# DSO_ADC.net
KiCad netlist of a schematic drawn in Altium Designer
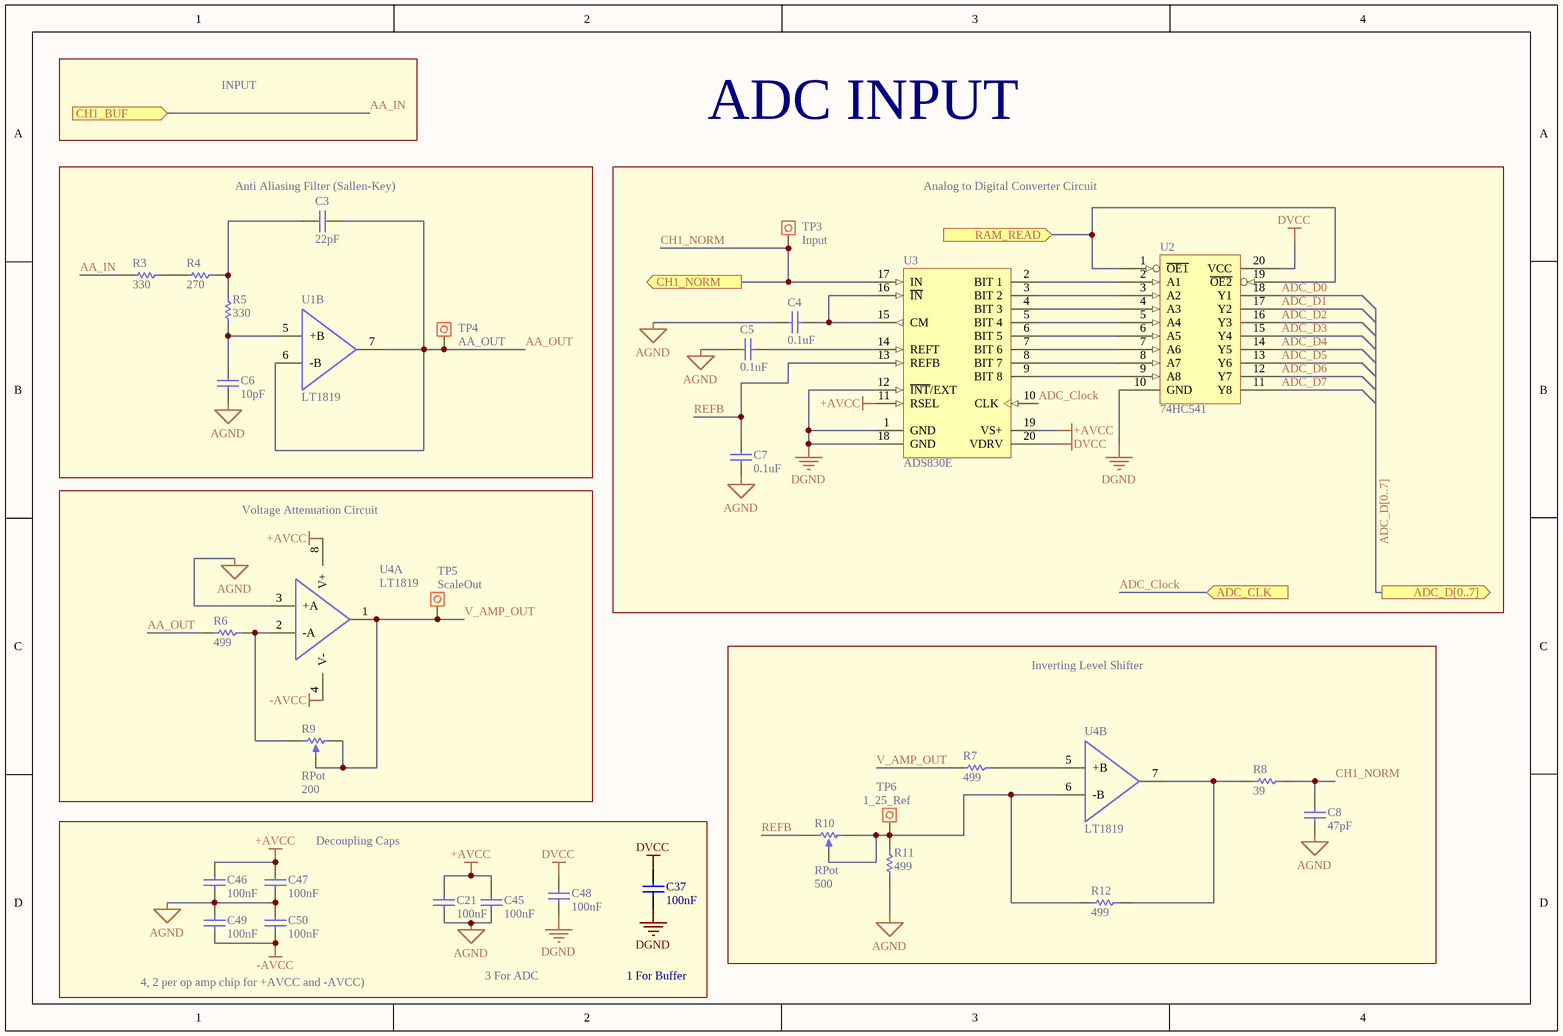
[diagram p0: DSO_ADC.SchDoc]

(export (version "E")
  (design (tool "Eeschema 10.0.6"))
  (components
    (comp (ref "C3")
      (value "22pF")
      (footprint "0805C")
      (description "Capacitor")
      (fields (field (name "REVIEWED BY") "RM - 2018/08/05"))
      (libsource (lib "DSO") (part "C"))
    )
    (comp (ref "C4")
      (value "0.1uF")
      (footprint "0805C")
      (description "Capacitor")
      (fields (field (name "REVIEWED BY") "RM - 2018/08/05"))
      (libsource (lib "DSO") (part "C"))
    )
    (comp (ref "C5")
      (value "0.1uF")
      (footprint "0805C")
      (description "Capacitor")
      (fields (field (name "REVIEWED BY") "RM - 2018/08/05"))
      (libsource (lib "DSO") (part "C"))
    )
    (comp (ref "C6")
      (value "10pF")
      (footprint "0805C")
      (description "Capacitor")
      (fields (field (name "REVIEWED BY") "RM - 2018/08/05"))
      (libsource (lib "DSO") (part "C"))
    )
    (comp (ref "C7")
      (value "0.1uF")
      (footprint "0805C")
      (description "Capacitor")
      (fields (field (name "REVIEWED BY") "RM - 2018/08/05"))
      (libsource (lib "DSO") (part "C"))
    )
    (comp (ref "C8")
      (value "47pF")
      (footprint "0805C")
      (description "Capacitor")
      (fields (field (name "REVIEWED BY") "RM - 2018/08/05"))
      (libsource (lib "DSO") (part "C"))
    )
    (comp (ref "C21")
      (value "100nF")
      (footprint "0805C")
      (description "Capacitor")
      (fields (field (name "REVIEWED BY") "RM - 2018/08/05"))
      (libsource (lib "DSO") (part "C"))
    )
    (comp (ref "C37")
      (value "100nF")
      (footprint "0805C")
      (description "Capacitor")
      (fields (field (name "REVIEWED BY") "RM - 2018/08/05"))
      (libsource (lib "DSO") (part "C"))
    )
    (comp (ref "C45")
      (value "100nF")
      (footprint "0805C")
      (description "Capacitor")
      (fields (field (name "REVIEWED BY") "RM - 2018/08/05"))
      (libsource (lib "DSO") (part "C"))
    )
    (comp (ref "C46")
      (value "100nF")
      (footprint "0805C")
      (description "Capacitor")
      (fields (field (name "REVIEWED BY") "RM - 2018/08/05"))
      (libsource (lib "DSO") (part "C"))
    )
    (comp (ref "C47")
      (value "100nF")
      (footprint "0805C")
      (description "Capacitor")
      (fields (field (name "REVIEWED BY") "RM - 2018/08/05"))
      (libsource (lib "DSO") (part "C"))
    )
    (comp (ref "C48")
      (value "100nF")
      (footprint "0805C")
      (description "Capacitor")
      (fields (field (name "REVIEWED BY") "RM - 2018/08/05"))
      (libsource (lib "DSO") (part "C"))
    )
    (comp (ref "C49")
      (value "100nF")
      (footprint "0805C")
      (description "Capacitor")
      (fields (field (name "REVIEWED BY") "RM - 2018/08/05"))
      (libsource (lib "DSO") (part "C"))
    )
    (comp (ref "C50")
      (value "100nF")
      (footprint "0805C")
      (description "Capacitor")
      (fields (field (name "REVIEWED BY") "RM - 2018/08/05"))
      (libsource (lib "DSO") (part "C"))
    )
    (comp (ref "R3")
      (value "330")
      (footprint "0805")
      (description "Resistor")
      (fields (field (name "REVIEWED BY") "RM - 2018/08/05"))
      (libsource (lib "DSO") (part "R"))
    )
    (comp (ref "R4")
      (value "270")
      (footprint "0805")
      (description "Resistor")
      (fields (field (name "REVIEWED BY") "RM - 2018/08/05"))
      (libsource (lib "DSO") (part "R"))
    )
    (comp (ref "R5")
      (value "330")
      (footprint "0805")
      (description "Resistor")
      (fields (field (name "REVIEWED BY") "RM - 2018/08/05"))
      (libsource (lib "DSO") (part "R"))
    )
    (comp (ref "R6")
      (value "499")
      (footprint "0805")
      (description "Resistor")
      (fields (field (name "REVIEWED BY") "RM - 2018/08/05"))
      (libsource (lib "DSO") (part "R"))
    )
    (comp (ref "R7")
      (value "499")
      (footprint "0805")
      (description "Resistor")
      (fields (field (name "REVIEWED BY") "RM - 2018/08/05"))
      (libsource (lib "DSO") (part "R"))
    )
    (comp (ref "R8")
      (value "39")
      (footprint "0805")
      (description "Resistor")
      (fields (field (name "REVIEWED BY") "RM - 2018/08/05"))
      (libsource (lib "DSO") (part "R"))
    )
    (comp (ref "R9")
      (value "RPot")
      (footprint "VR5")
      (description "Potentiometer")
      (fields (field (name "ALTIUM_VALUE") "200") (field (name "PUBLISHER") "Altium Limited"))
      (libsource (lib "DSO") (part "RPot"))
    )
    (comp (ref "R10")
      (value "RPot")
      (footprint "VR5")
      (description "Potentiometer")
      (fields (field (name "ALTIUM_VALUE") "500") (field (name "PUBLISHER") "Altium Limited"))
      (libsource (lib "DSO") (part "RPot"))
    )
    (comp (ref "R11")
      (value "499")
      (footprint "0805")
      (description "Resistor")
      (fields (field (name "REVIEWED BY") "RM - 2018/08/05"))
      (libsource (lib "DSO") (part "R"))
    )
    (comp (ref "R12")
      (value "499")
      (footprint "0805")
      (description "Resistor")
      (fields (field (name "REVIEWED BY") "RM - 2018/08/05"))
      (libsource (lib "DSO") (part "R"))
    )
    (comp (ref "TP3")
      (value "Input")
      (footprint "Testpoin")
      (description "Pad")
      (fields (field (name "Comment") "INPUT"))
      (libsource (lib "DSO") (part "Test Point"))
    )
    (comp (ref "TP4")
      (value "AA_OUT")
      (footprint "Testpoin")
      (description "Pad")
      (fields (field (name "Comment") "INPUT"))
      (libsource (lib "DSO") (part "Test Point"))
    )
    (comp (ref "TP5")
      (value "ScaleOut")
      (footprint "Testpoin")
      (description "Pad")
      (fields (field (name "Comment") "INPUT"))
      (libsource (lib "DSO") (part "Test Point"))
    )
    (comp (ref "TP6")
      (value "1_25_Ref")
      (footprint "Testpoin")
      (description "Pad")
      (fields (field (name "Comment") "INPUT"))
      (libsource (lib "DSO") (part "Test Point"))
    )
    (comp (ref "U1")
      (value "LT1819")
      (footprint "SOIC-8")
      (description "OpAmp High Frequency Dual")
      (fields (field (name "REVIEWED BY") "RM - 2018/08/05"))
      (libsource (lib "DSO") (part "LT1819"))
    )
    (comp (ref "U2")
      (value "74HC541")
      (footprint "SOT163-1_N")
      (description "(ADV) Octal Buffer, Line Driver")
      (fields (field (name "REVIEWED BY") "RM - 2018/08/05"))
      (libsource (lib "DSO") (part "74HC541"))
    )
    (comp (ref "U3")
      (value "ADS830E")
      (footprint "TI-DBQ20_L")
      (fields (field (name "REVIEWED BY") "RM - 2018/08/05"))
      (libsource (lib "DSO") (part "ADS830E"))
    )
    (comp (ref "U4")
      (value "LT1819")
      (footprint "SOIC-8")
      (description "OpAmp High Frequency Dual")
      (fields (field (name "REVIEWED BY") "RM - 2018/08/05"))
      (libsource (lib "DSO") (part "LT1819"))
    )
  )
  (nets
    (net (code "1") (name "+AVCC") (class "Default")
      (node (ref "C21") (pin "1") (pinfunction "1_1") (pintype "passive"))
      (node (ref "C45") (pin "1") (pinfunction "1_1") (pintype "passive"))
      (node (ref "C46") (pin "1") (pinfunction "1_1") (pintype "passive"))
      (node (ref "C47") (pin "1") (pinfunction "1_1") (pintype "passive"))
      (node (ref "U3") (pin "11") (pinfunction "RSEL_11") (pintype "input"))
      (node (ref "U3") (pin "19") (pinfunction "VS+_19") (pintype "power_in"))
      (node (ref "U4") (pin "8") (pinfunction "V+_8") (pintype "passive"))
    )
    (net (code "2") (name "-AVCC") (class "Default")
      (node (ref "C49") (pin "1") (pinfunction "1_1") (pintype "passive"))
      (node (ref "C50") (pin "1") (pinfunction "1_1") (pintype "passive"))
      (node (ref "U4") (pin "4") (pinfunction "V-_4") (pintype "passive"))
    )
    (net (code "3") (name "/AA_IN") (class "Default") (node (ref "R3") (pin "2") (pintype "passive")))
    (net (code "4") (name "/AA_OUT") (class "Default")
      (node (ref "C3") (pin "1") (pinfunction "1_1") (pintype "passive"))
      (node (ref "R6") (pin "2") (pintype "passive"))
      (node (ref "TP4") (pin "1") (pintype "passive"))
      (node (ref "U1") (pin "6") (pinfunction "-B_6") (pintype "passive"))
      (node (ref "U1") (pin "7") (pinfunction "OUTB_7") (pintype "passive"))
    )
    (net (code "5") (name "/ADC_Clock") (class "Default")
      (node (ref "U3") (pin "10") (pinfunction "CLK_10") (pintype "input"))
    )
    (net (code "6") (name "/ADC_D0") (class "Default")
      (node (ref "U2") (pin "18") (pinfunction "Y1_18") (pintype "tri_state"))
    )
    (net (code "7") (name "/ADC_D1") (class "Default")
      (node (ref "U2") (pin "17") (pinfunction "Y2_17") (pintype "tri_state"))
    )
    (net (code "8") (name "/ADC_D2") (class "Default")
      (node (ref "U2") (pin "16") (pinfunction "Y3_16") (pintype "tri_state"))
    )
    (net (code "9") (name "/ADC_D3") (class "Default")
      (node (ref "U2") (pin "15") (pinfunction "Y4_15") (pintype "tri_state"))
    )
    (net (code "10") (name "/ADC_D4") (class "Default")
      (node (ref "U2") (pin "14") (pinfunction "Y5_14") (pintype "tri_state"))
    )
    (net (code "11") (name "/ADC_D5") (class "Default")
      (node (ref "U2") (pin "13") (pinfunction "Y6_13") (pintype "tri_state"))
    )
    (net (code "12") (name "/ADC_D6") (class "Default")
      (node (ref "U2") (pin "12") (pinfunction "Y7_12") (pintype "tri_state"))
    )
    (net (code "13") (name "/ADC_D7") (class "Default")
      (node (ref "U2") (pin "11") (pinfunction "Y8_11") (pintype "tri_state"))
    )
    (net (code "15") (name "/CH1_NORM") (class "Default")
      (node (ref "C8") (pin "1") (pinfunction "1_1") (pintype "passive"))
      (node (ref "R8") (pin "1") (pintype "passive"))
      (node (ref "TP3") (pin "1") (pintype "passive"))
      (node (ref "U3") (pin "17") (pinfunction "IN_17") (pintype "input"))
    )
    (net (code "16") (name "/RAM_READ") (class "Default")
      (node (ref "U2") (pin "1") (pinfunction "~{OE1}_1") (pintype "input"))
      (node (ref "U2") (pin "19") (pinfunction "~{OE2}_19") (pintype "input"))
    )
    (net (code "17") (name "/REFB") (class "Default")
      (node (ref "C7") (pin "2") (pinfunction "2_2") (pintype "passive"))
      (node (ref "R10") (pin "1") (pinfunction "TOP_1") (pintype "passive"))
      (node (ref "U3") (pin "13") (pinfunction "REFB_13") (pintype "input"))
    )
    (net (code "18") (name "/V_AMP_OUT") (class "Default")
      (node (ref "R7") (pin "2") (pintype "passive"))
      (node (ref "R9") (pin "2") (pinfunction "TAP_2") (pintype "passive"))
      (node (ref "R9") (pin "3") (pinfunction "BOT_3") (pintype "passive"))
      (node (ref "TP5") (pin "1") (pintype "passive"))
      (node (ref "U4") (pin "1") (pinfunction "OUTA_1") (pintype "passive"))
    )
    (net (code "19") (name "AGND") (class "Default")
      (node (ref "C21") (pin "2") (pinfunction "2_2") (pintype "passive"))
      (node (ref "C4") (pin "1") (pinfunction "1_1") (pintype "passive"))
      (node (ref "C45") (pin "2") (pinfunction "2_2") (pintype "passive"))
      (node (ref "C46") (pin "2") (pinfunction "2_2") (pintype "passive"))
      (node (ref "C47") (pin "2") (pinfunction "2_2") (pintype "passive"))
      (node (ref "C49") (pin "2") (pinfunction "2_2") (pintype "passive"))
      (node (ref "C5") (pin "1") (pinfunction "1_1") (pintype "passive"))
      (node (ref "C50") (pin "2") (pinfunction "2_2") (pintype "passive"))
      (node (ref "C6") (pin "2") (pinfunction "2_2") (pintype "passive"))
      (node (ref "C7") (pin "1") (pinfunction "1_1") (pintype "passive"))
      (node (ref "C8") (pin "2") (pinfunction "2_2") (pintype "passive"))
      (node (ref "R11") (pin "2") (pintype "passive"))
      (node (ref "U4") (pin "3") (pinfunction "+A_3") (pintype "passive"))
    )
    (net (code "20") (name "DGND") (class "Default")
      (node (ref "C37") (pin "2") (pinfunction "2_2") (pintype "passive"))
      (node (ref "C48") (pin "2") (pinfunction "2_2") (pintype "passive"))
      (node (ref "U2") (pin "10") (pinfunction "GND_10") (pintype "power_in"))
      (node (ref "U3") (pin "1") (pinfunction "GND_1") (pintype "power_in"))
      (node (ref "U3") (pin "12") (pinfunction "~{INT}/EXT_12") (pintype "input"))
      (node (ref "U3") (pin "18") (pinfunction "GND_18") (pintype "power_in"))
    )
    (net (code "21") (name "DVCC") (class "Default")
      (node (ref "C37") (pin "1") (pinfunction "1_1") (pintype "passive"))
      (node (ref "C48") (pin "1") (pinfunction "1_1") (pintype "passive"))
      (node (ref "U2") (pin "20") (pinfunction "VCC_20") (pintype "power_in"))
      (node (ref "U3") (pin "20") (pinfunction "VDRV_20") (pintype "power_in"))
    )
    (net (code "22") (name "Net-(C3-Pad2)") (class "Default")
      (node (ref "C3") (pin "2") (pinfunction "2_2") (pintype "passive"))
      (node (ref "R4") (pin "1") (pintype "passive"))
      (node (ref "R5") (pin "1") (pintype "passive"))
    )
    (net (code "23") (name "Net-(R3-Pad1)") (class "Default")
      (node (ref "R3") (pin "1") (pintype "passive"))
      (node (ref "R4") (pin "2") (pintype "passive"))
    )
    (net (code "24") (name "Net-(R9-TOP)") (class "Default")
      (node (ref "R6") (pin "1") (pintype "passive"))
      (node (ref "R9") (pin "1") (pinfunction "TOP_1") (pintype "passive"))
      (node (ref "U4") (pin "2") (pinfunction "-A_2") (pintype "passive"))
    )
    (net (code "25") (name "Net-(R10-BOT)") (class "Default")
      (node (ref "R10") (pin "2") (pinfunction "TAP_2") (pintype "passive"))
      (node (ref "R10") (pin "3") (pinfunction "BOT_3") (pintype "passive"))
      (node (ref "R11") (pin "1") (pintype "passive"))
      (node (ref "R12") (pin "2") (pintype "passive"))
      (node (ref "TP6") (pin "1") (pintype "passive"))
      (node (ref "U4") (pin "6") (pinfunction "-B_6") (pintype "passive"))
    )
    (net (code "26") (name "Net-(U1B-+B)") (class "Default")
      (node (ref "C6") (pin "1") (pinfunction "1_1") (pintype "passive"))
      (node (ref "R5") (pin "2") (pintype "passive"))
      (node (ref "U1") (pin "5") (pinfunction "+B_5") (pintype "passive"))
    )
    (net (code "27") (name "Net-(U2-A1)") (class "Default")
      (node (ref "U2") (pin "2") (pinfunction "A1_2") (pintype "input"))
      (node (ref "U3") (pin "2") (pinfunction "BIT_1_2") (pintype "tri_state"))
    )
    (net (code "28") (name "Net-(U2-A2)") (class "Default")
      (node (ref "U2") (pin "3") (pinfunction "A2_3") (pintype "input"))
      (node (ref "U3") (pin "3") (pinfunction "BIT_2_3") (pintype "tri_state"))
    )
    (net (code "29") (name "Net-(U2-A3)") (class "Default")
      (node (ref "U2") (pin "4") (pinfunction "A3_4") (pintype "input"))
      (node (ref "U3") (pin "4") (pinfunction "BIT_3_4") (pintype "tri_state"))
    )
    (net (code "30") (name "Net-(U2-A4)") (class "Default")
      (node (ref "U2") (pin "5") (pinfunction "A4_5") (pintype "input"))
      (node (ref "U3") (pin "5") (pinfunction "BIT_4_5") (pintype "tri_state"))
    )
    (net (code "31") (name "Net-(U2-A5)") (class "Default")
      (node (ref "U2") (pin "6") (pinfunction "A5_6") (pintype "input"))
      (node (ref "U3") (pin "6") (pinfunction "BIT_5_6") (pintype "tri_state"))
    )
    (net (code "32") (name "Net-(U2-A6)") (class "Default")
      (node (ref "U2") (pin "7") (pinfunction "A6_7") (pintype "input"))
      (node (ref "U3") (pin "7") (pinfunction "BIT_6_7") (pintype "tri_state"))
    )
    (net (code "33") (name "Net-(U2-A7)") (class "Default")
      (node (ref "U2") (pin "8") (pinfunction "A7_8") (pintype "input"))
      (node (ref "U3") (pin "8") (pinfunction "BIT_7_8") (pintype "tri_state"))
    )
    (net (code "34") (name "Net-(U2-A8)") (class "Default")
      (node (ref "U2") (pin "9") (pinfunction "A8_9") (pintype "input"))
      (node (ref "U3") (pin "9") (pinfunction "BIT_8_9") (pintype "tri_state"))
    )
    (net (code "35") (name "Net-(U3-CM)") (class "Default")
      (node (ref "C4") (pin "2") (pinfunction "2_2") (pintype "passive"))
      (node (ref "U3") (pin "15") (pinfunction "CM_15") (pintype "output"))
      (node (ref "U3") (pin "16") (pinfunction "~{IN}_16") (pintype "input"))
    )
    (net (code "36") (name "Net-(U3-REFT)") (class "Default")
      (node (ref "C5") (pin "2") (pinfunction "2_2") (pintype "passive"))
      (node (ref "U3") (pin "14") (pinfunction "REFT_14") (pintype "input"))
    )
    (net (code "37") (name "Net-(U4B-+B)") (class "Default")
      (node (ref "R7") (pin "1") (pintype "passive"))
      (node (ref "U4") (pin "5") (pinfunction "+B_5") (pintype "passive"))
    )
    (net (code "38") (name "Net-(U4B-OUTB)") (class "Default")
      (node (ref "R12") (pin "1") (pintype "passive"))
      (node (ref "R8") (pin "2") (pintype "passive"))
      (node (ref "U4") (pin "7") (pinfunction "OUTB_7") (pintype "passive"))
    )
  )
)
